# Final_v2.net
KiCad netlist of a schematic drawn in EAGLE
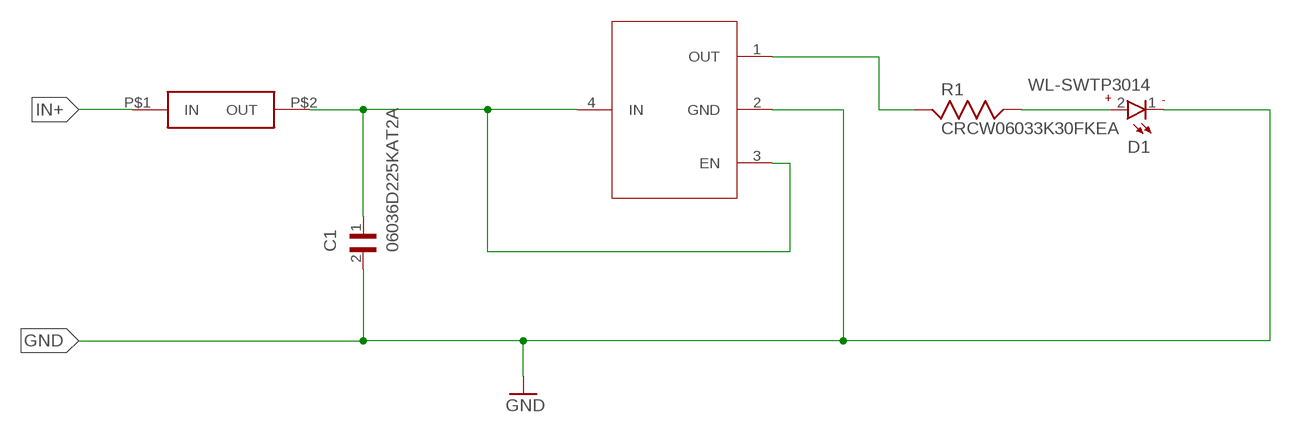
[diagram p0: schematic, sheet 1]

(export (version "E")
  (design (tool "Eeschema 10.0.6"))
  (components
    (comp (ref "C1")
      (value "06036D225KAT2A")
      (footprint "eagle-import:CAPC1608X90")
      (fields (field (name "DIGI-KEY_PART_NUMBER") "478-1252-1-ND") (field (name "MF") "AVX"))
      (libsource (lib "eagle-import") (part "06036D225KAT2A"))
    )
    (comp (ref "D1")
      (value "WL-SWTP3014")
      (footprint "eagle-import:WL-SWTP_3014")
      (fields
        (field (name "DIGI-KEY_PART_NUMBER") "732-5661-1-ND")
        (field (name "MF") "Wurth Electronics")
        (field (name "MP") "158301250")
      )
      (libsource (lib "eagle-import") (part "WL-SWTP3014"))
    )
    (comp (ref "R1")
      (value "CRCW06033K30FKEA")
      (footprint "eagle-import:RESC1608X55")
      (fields (field (name "DIGI-KEY_PART_NUMBER") "541-3.30KHCT-ND") (field (name "MF") "Vishay Dale"))
      (libsource (lib "eagle-import") (part "CRCW06033K30FKEA"))
    )
    (comp (ref "U$2")
      (value "SCHOTTKY0402")
      (footprint "eagle-import:0402_MURATA")
      (libsource (lib "eagle-import") (part "SCHOTTKY0402"))
    )
    (comp (ref "U$3")
      (value "NCP161_711AJ")
      (footprint "eagle-import:REG_NCP160AMX180TBG")
      (libsource (lib "eagle-import") (part "NCP161_711AJ"))
    )
  )
  (nets
    (net (code "1") (name "GND") (class "Default")
      (node (ref "C1") (pin "2") (pinfunction "2_2") (pintype "passive"))
      (node (ref "D1") (pin "1") (pinfunction "1_1") (pintype "bidirectional"))
      (node (ref "U$3") (pin "2") (pinfunction "GND_2") (pintype "bidirectional"))
    )
    (net (code "2") (name "IN+") (class "Default")
      (node (ref "U$2") (pin "P$1") (pinfunction "IN_P$1") (pintype "bidirectional"))
    )
    (net (code "3") (name "Net-(D1-Pad2)") (class "Default")
      (node (ref "D1") (pin "2") (pinfunction "2_2") (pintype "bidirectional"))
      (node (ref "R1") (pin "2") (pinfunction "2_2") (pintype "passive"))
    )
    (net (code "4") (name "Net-(U$2-OUT)") (class "Default")
      (node (ref "C1") (pin "1") (pinfunction "1_1") (pintype "passive"))
      (node (ref "U$2") (pin "P$2") (pinfunction "OUT_P$2") (pintype "bidirectional"))
      (node (ref "U$3") (pin "3") (pinfunction "EN_3") (pintype "bidirectional"))
      (node (ref "U$3") (pin "4") (pinfunction "IN_4") (pintype "bidirectional"))
    )
    (net (code "5") (name "Net-(U$3-OUT)") (class "Default")
      (node (ref "R1") (pin "1") (pinfunction "1_1") (pintype "passive"))
      (node (ref "U$3") (pin "1") (pinfunction "OUT_1") (pintype "bidirectional"))
    )
  )
)
